# power.net
KiCad netlist of a schematic drawn in Altium Designer
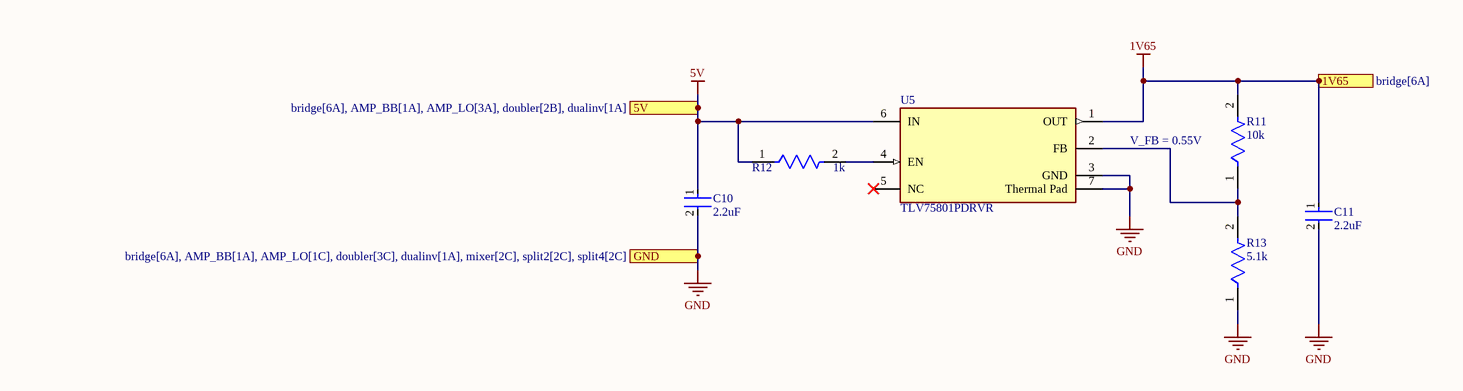
[diagram p0: power.SchDoc]

(export (version "E")
  (design (tool "Eeschema 10.0.6"))
  (components
    (comp (ref "C10")
      (value "2.2uF")
      (footprint "FP-GRM188-0_1-e0_2_0_5-MFG")
      (description "Chip Multilayer Ceramic Capacitors for General Purpose, 0603, 2.2uF, X7R, 15%, 10%, 10V")
      (fields (field (name "VOLTAGE") "10V") (field (name "TOLERANCE") "10%"))
      (libsource (lib "FullLib") (part "CMP-2006-02836-2"))
    )
    (comp (ref "C11")
      (value "2.2uF")
      (footprint "FP-GRM188-0_1-e0_2_0_5-MFG")
      (description "Chip Multilayer Ceramic Capacitors for General Purpose, 0603, 2.2uF, X7R, 15%, 10%, 10V")
      (fields (field (name "VOLTAGE") "10V") (field (name "TOLERANCE") "10%"))
      (libsource (lib "FullLib") (part "CMP-2006-02836-2"))
    )
    (comp (ref "R11")
      (value "10k")
      (footprint "FP-RC0603-0_55-IPC_C")
      (description "RES 10K OHM 1% 1/10W 0603")
      (fields (field (name "TOLERANCE") "1%") (field (name "PART NUMBER") "ERJ-S03F1002V"))
      (libsource (lib "FullLib") (part "CMP-2100-03664-2"))
    )
    (comp (ref "R12")
      (value "1k")
      (footprint "FP-ERJ3G-MFG")
      (description "RES SMD 1K OHM 5% 1/10W 0603")
      (fields (field (name "VOLTAGE") "75 V") (field (name "MANUFACTURER") "Panasonic"))
      (libsource (lib "FullLib") (part "CMP-2000-00703-2"))
    )
    (comp (ref "R13")
      (value "5.1k")
      (footprint "FP-CRCW0603-e3-IPC_C")
      (description "RES Thick Film, 5.1kΩ, 1%, 0.1W, 100ppm/°C, 0603")
      (fields (field (name "TOLERANCE") "1%") (field (name "PART NUMBER") "ERJ-3EKF5101V"))
      (libsource (lib "FullLib") (part "CMP-1012-00590-3"))
    )
    (comp (ref "U5")
      (value "TLV75801PDRVR")
      (footprint "FP-DRV0006A-MFG")
      (description "IC REG LIN POS ADJ 500MA 6WSON")
      (fields (field (name "MANUFACTURER") "Texas Instruments"))
      (libsource (lib "FullLib") (part "CMP-04917-000312-1"))
    )
  )
  (nets
    (net (code "1") (name "1V65") (class "Default")
      (node (ref "C11") (pin "1") (pinfunction "1_1") (pintype "passive"))
      (node (ref "R11") (pin "2") (pinfunction "2_2") (pintype "passive"))
      (node (ref "U5") (pin "1") (pinfunction "OUT_1") (pintype "output"))
    )
    (net (code "2") (name "5V") (class "Default")
      (node (ref "C10") (pin "1") (pinfunction "1_1") (pintype "passive"))
      (node (ref "R12") (pin "1") (pinfunction "1_1") (pintype "passive"))
      (node (ref "U5") (pin "6") (pinfunction "IN_6") (pintype "power_in"))
    )
    (net (code "3") (name "GND") (class "Default")
      (node (ref "C10") (pin "2") (pinfunction "2_2") (pintype "passive"))
      (node (ref "C11") (pin "2") (pinfunction "2_2") (pintype "passive"))
      (node (ref "R13") (pin "1") (pinfunction "1_1") (pintype "passive"))
      (node (ref "U5") (pin "3") (pinfunction "GND_3") (pintype "power_in"))
      (node (ref "U5") (pin "7") (pinfunction "Thermal_Pad_7") (pintype "power_in"))
    )
    (net (code "4") (name "Net-(U5-EN)") (class "Default")
      (node (ref "R12") (pin "2") (pinfunction "2_2") (pintype "passive"))
      (node (ref "U5") (pin "4") (pinfunction "EN_4") (pintype "input"))
    )
    (net (code "5") (name "Net-(U5-FB)") (class "Default")
      (node (ref "R11") (pin "1") (pinfunction "1_1") (pintype "passive"))
      (node (ref "R13") (pin "2") (pinfunction "2_2") (pintype "passive"))
      (node (ref "U5") (pin "2") (pinfunction "FB_2") (pintype "passive"))
    )
    (net (code "6") (name "unconnected-(U5-NC-Pad5)") (class "Default")
      (node (ref "U5") (pin "5") (pinfunction "NC_5") (pintype "passive+no_connect"))
    )
  )
)
